# emp3032a.net
KiCad netlist of a schematic drawn in EAGLE
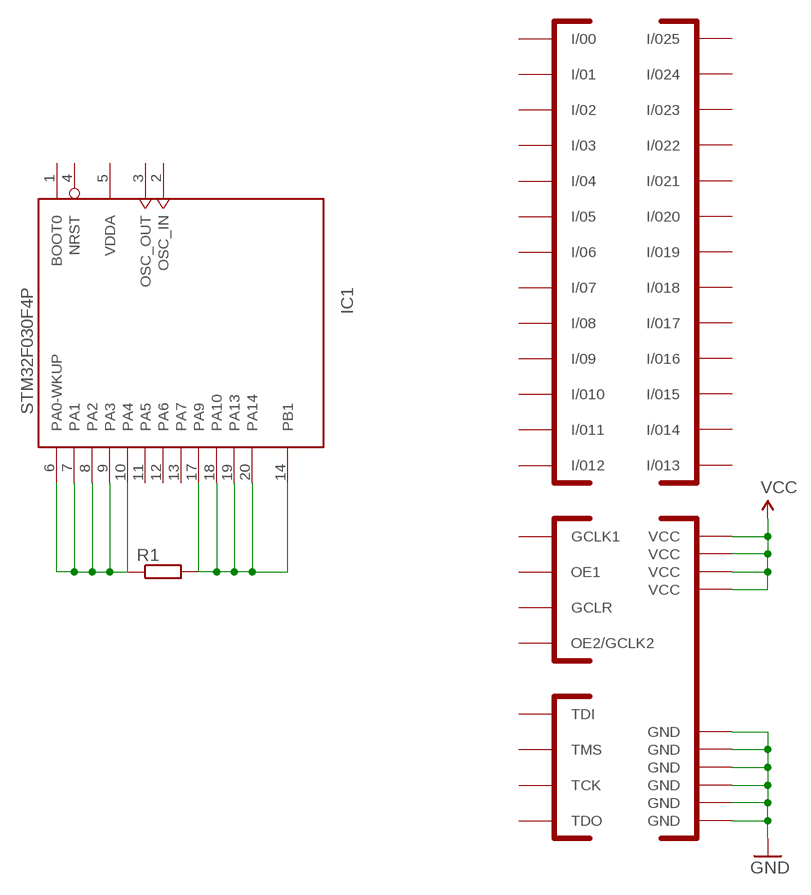
[diagram p0: schematic, sheet 1]
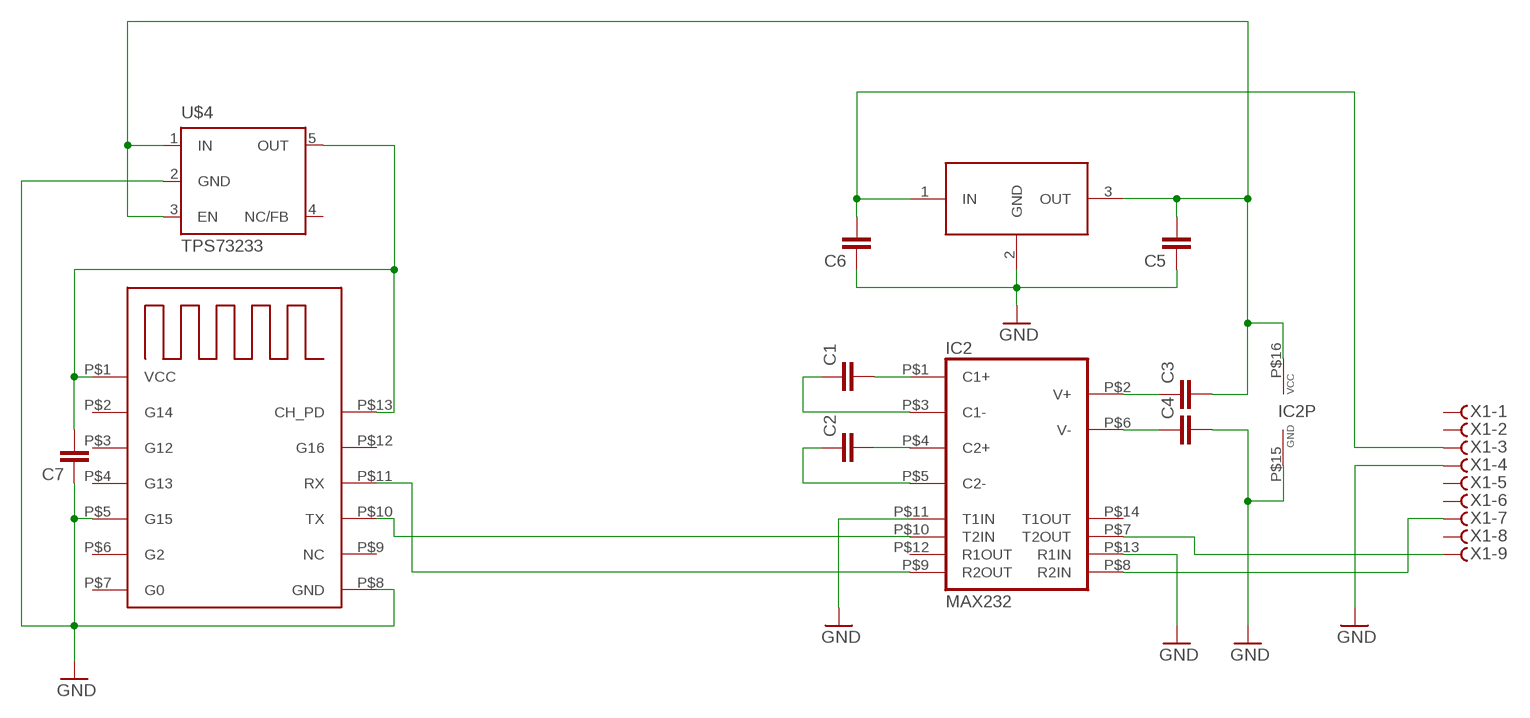
[diagram p1: schematic, sheet 2]

(export (version "E")
  (design (tool "Eeschema 10.0.6"))
  (components
    (comp (ref "IC1")
      (value "STM32F030F4P")
      (footprint "eagle-import:TSSOP20-I")
      (libsource (lib "eagle-import") (part "STM32F030FP4"))
    )
    (comp (ref "R1")
      (value "R1206")
      (footprint "eagle-import:R1206")
      (libsource (lib "eagle-import") (part "R1206"))
    )
    (comp (ref "U$1")
      (value "EPM3032")
      (footprint "eagle-import:TQFP44")
      (libsource (lib "eagle-import") (part "EPM3032"))
    )
    (comp (ref "C1")
      (value "C-EUC1206K")
      (footprint "eagle-import:C1206K")
      (libsource (lib "eagle-import") (part "C-EUC1206K"))
    )
    (comp (ref "C2")
      (value "C-EUC1206K")
      (footprint "eagle-import:C1206K")
      (libsource (lib "eagle-import") (part "C-EUC1206K"))
    )
    (comp (ref "C3")
      (value "C-EUC1206K")
      (footprint "eagle-import:C1206K")
      (libsource (lib "eagle-import") (part "C-EUC1206K"))
    )
    (comp (ref "C4")
      (value "C-EUC1206K")
      (footprint "eagle-import:C1206K")
      (libsource (lib "eagle-import") (part "C-EUC1206K"))
    )
    (comp (ref "C5")
      (value "C-EUC1206K")
      (footprint "eagle-import:C1206K")
      (libsource (lib "eagle-import") (part "C-EUC1206K"))
    )
    (comp (ref "C6")
      (value "C-EUC1206K")
      (footprint "eagle-import:C1206K")
      (libsource (lib "eagle-import") (part "C-EUC1206K"))
    )
    (comp (ref "C7")
      (value "C-EUC1206K")
      (footprint "eagle-import:C1206K")
      (libsource (lib "eagle-import") (part "C-EUC1206K"))
    )
    (comp (ref "IC2")
      (value "MAX232")
      (footprint "eagle-import:DIL16")
      (libsource (lib "eagle-import") (part "MAX232"))
    )
    (comp (ref "U$2")
      (value "ESP03")
      (footprint "eagle-import:ESP03")
      (libsource (lib "eagle-import") (part "ESP03"))
    )
    (comp (ref "U$3")
      (value "LM78M05BG")
      (footprint "eagle-import:DPACK")
      (libsource (lib "eagle-import") (part "LM78M05BG"))
    )
    (comp (ref "U$4")
      (value "TPS73233")
      (footprint "eagle-import:SOT23-DBV")
      (libsource (lib "eagle-import") (part "TPS73233"))
    )
    (comp (ref "X1")
      (value "F09HS")
      (footprint "eagle-import:F09H")
      (libsource (lib "eagle-import") (part "F09?SH"))
    )
  )
  (nets
    (net (code "1") (name "GCLK1") (class "Default")
      (node (ref "U$1") (pin "37") (pinfunction "GCLK1_37") (pintype "power_in"))
    )
    (net (code "2") (name "GCLR") (class "Default")
      (node (ref "U$1") (pin "39") (pinfunction "GCLR_39") (pintype "power_in"))
    )
    (net (code "3") (name "GND") (class "Default")
      (node (ref "C4") (pin "2") (pinfunction "2_2") (pintype "passive"))
      (node (ref "C5") (pin "1") (pinfunction "1_1") (pintype "passive"))
      (node (ref "C6") (pin "1") (pinfunction "1_1") (pintype "passive"))
      (node (ref "C7") (pin "1") (pinfunction "1_1") (pintype "passive"))
      (node (ref "IC2") (pin "P$11") (pinfunction "T1IN_P$11") (pintype "input"))
      (node (ref "IC2") (pin "P$13") (pinfunction "R1IN_P$13") (pintype "input"))
      (node (ref "IC2") (pin "P$15") (pinfunction "GND_P$15") (pintype "power_in"))
      (node (ref "U$1") (pin "11") (pinfunction "GND_11") (pintype "power_in"))
      (node (ref "U$1") (pin "16") (pinfunction "GND_16") (pintype "power_in"))
      (node (ref "U$1") (pin "24") (pinfunction "GND_24") (pintype "power_in"))
      (node (ref "U$1") (pin "30") (pinfunction "GND_30") (pintype "power_in"))
      (node (ref "U$1") (pin "36") (pinfunction "GND_36") (pintype "power_in"))
      (node (ref "U$1") (pin "4") (pinfunction "GND_4") (pintype "power_in"))
      (node (ref "U$2") (pin "P$5") (pinfunction "G15_P$5") (pintype "bidirectional"))
      (node (ref "U$2") (pin "P$8") (pinfunction "GND_P$8") (pintype "bidirectional"))
      (node (ref "U$3") (pin "2") (pinfunction "GND_2") (pintype "bidirectional"))
      (node (ref "U$4") (pin "2") (pinfunction "GND_2") (pintype "power_in"))
      (node (ref "X1") (pin "4") (pinfunction "F_4") (pintype "passive"))
    )
    (net (code "4") (name "I{slash}00") (class "Default")
      (node (ref "U$1") (pin "2") (pinfunction "I/00_2") (pintype "power_in"))
    )
    (net (code "5") (name "I{slash}01") (class "Default")
      (node (ref "U$1") (pin "5") (pinfunction "I/01_5") (pintype "power_in"))
    )
    (net (code "6") (name "I{slash}02") (class "Default")
      (node (ref "U$1") (pin "6") (pinfunction "I/02_6") (pintype "power_in"))
    )
    (net (code "7") (name "I{slash}03") (class "Default")
      (node (ref "U$1") (pin "12") (pinfunction "I/03_12") (pintype "power_in"))
    )
    (net (code "8") (name "I{slash}04") (class "Default")
      (node (ref "U$1") (pin "13") (pinfunction "I/04_13") (pintype "power_in"))
    )
    (net (code "9") (name "I{slash}05") (class "Default")
      (node (ref "U$1") (pin "14") (pinfunction "I/05_14") (pintype "power_in"))
    )
    (net (code "10") (name "I{slash}06") (class "Default")
      (node (ref "U$1") (pin "15") (pinfunction "I/06_15") (pintype "power_in"))
    )
    (net (code "11") (name "I{slash}07") (class "Default")
      (node (ref "U$1") (pin "25") (pinfunction "I/07_25") (pintype "power_in"))
    )
    (net (code "12") (name "I{slash}08") (class "Default")
      (node (ref "U$1") (pin "44") (pinfunction "I/08_44") (pintype "power_in"))
    )
    (net (code "13") (name "I{slash}09") (class "Default")
      (node (ref "U$1") (pin "43") (pinfunction "I/09_43") (pintype "power_in"))
    )
    (net (code "14") (name "I{slash}010") (class "Default")
      (node (ref "U$1") (pin "42") (pinfunction "I/010_42") (pintype "power_in"))
    )
    (net (code "15") (name "I{slash}011") (class "Default")
      (node (ref "U$1") (pin "35") (pinfunction "I/011_35") (pintype "power_in"))
    )
    (net (code "16") (name "I{slash}012") (class "Default")
      (node (ref "U$1") (pin "34") (pinfunction "I/012_34") (pintype "power_in"))
    )
    (net (code "17") (name "I{slash}013") (class "Default")
      (node (ref "U$1") (pin "28") (pinfunction "I/013_28") (pintype "power_in"))
    )
    (net (code "18") (name "I{slash}014") (class "Default")
      (node (ref "U$1") (pin "27") (pinfunction "I/014_27") (pintype "power_in"))
    )
    (net (code "19") (name "I{slash}015") (class "Default")
      (node (ref "U$1") (pin "33") (pinfunction "I/015_33") (pintype "power_in"))
    )
    (net (code "20") (name "I{slash}016") (class "Default")
      (node (ref "U$1") (pin "21") (pinfunction "I/016_21") (pintype "power_in"))
    )
    (net (code "21") (name "I{slash}017") (class "Default")
      (node (ref "U$1") (pin "22") (pinfunction "I/017_22") (pintype "power_in"))
    )
    (net (code "22") (name "I{slash}018") (class "Default")
      (node (ref "U$1") (pin "23") (pinfunction "I/018_23") (pintype "power_in"))
    )
    (net (code "23") (name "I{slash}019") (class "Default")
      (node (ref "U$1") (pin "31") (pinfunction "I/019_31") (pintype "power_in"))
    )
    (net (code "24") (name "I{slash}020") (class "Default")
      (node (ref "U$1") (pin "18") (pinfunction "I/020_18") (pintype "power_in"))
    )
    (net (code "25") (name "I{slash}021") (class "Default")
      (node (ref "U$1") (pin "19") (pinfunction "I/021_19") (pintype "power_in"))
    )
    (net (code "26") (name "I{slash}022") (class "Default")
      (node (ref "U$1") (pin "8") (pinfunction "I/022_8") (pintype "power_in"))
    )
    (net (code "27") (name "I{slash}023") (class "Default")
      (node (ref "U$1") (pin "20") (pinfunction "I/023_20") (pintype "power_in"))
    )
    (net (code "28") (name "I{slash}024") (class "Default")
      (node (ref "U$1") (pin "10") (pinfunction "I/024_10") (pintype "power_in"))
    )
    (net (code "29") (name "I{slash}025") (class "Default")
      (node (ref "U$1") (pin "3") (pinfunction "I/025_3") (pintype "power_in"))
    )
    (net (code "30") (name "Net-(IC1A-PA0-WKUP)") (class "Default")
      (node (ref "IC1") (pin "10") (pinfunction "PA4_10") (pintype "bidirectional"))
      (node (ref "IC1") (pin "6") (pinfunction "PA0-WKUP_6") (pintype "bidirectional"))
      (node (ref "IC1") (pin "7") (pinfunction "PA1_7") (pintype "bidirectional"))
      (node (ref "IC1") (pin "8") (pinfunction "PA2_8") (pintype "bidirectional"))
      (node (ref "IC1") (pin "9") (pinfunction "PA3_9") (pintype "bidirectional"))
      (node (ref "R1") (pin "1") (pinfunction "1_1") (pintype "passive"))
    )
    (net (code "31") (name "Net-(IC1A-PA10)") (class "Default")
      (node (ref "IC1") (pin "14") (pinfunction "PB1_14") (pintype "bidirectional"))
      (node (ref "IC1") (pin "17") (pinfunction "PA9_17") (pintype "bidirectional"))
      (node (ref "IC1") (pin "18") (pinfunction "PA10_18") (pintype "bidirectional"))
      (node (ref "IC1") (pin "19") (pinfunction "PA13_19") (pintype "bidirectional"))
      (node (ref "IC1") (pin "20") (pinfunction "PA14_20") (pintype "bidirectional"))
      (node (ref "R1") (pin "2") (pinfunction "2_2") (pintype "passive"))
    )
    (net (code "32") (name "Net-(IC2A-C1+)") (class "Default")
      (node (ref "C1") (pin "2") (pinfunction "2_2") (pintype "passive"))
      (node (ref "IC2") (pin "P$1") (pinfunction "C1+_P$1") (pintype "bidirectional"))
    )
    (net (code "33") (name "Net-(IC2A-C1-)") (class "Default")
      (node (ref "C1") (pin "1") (pinfunction "1_1") (pintype "passive"))
      (node (ref "IC2") (pin "P$3") (pinfunction "C1-_P$3") (pintype "bidirectional"))
    )
    (net (code "34") (name "Net-(IC2A-C2+)") (class "Default")
      (node (ref "C2") (pin "2") (pinfunction "2_2") (pintype "passive"))
      (node (ref "IC2") (pin "P$4") (pinfunction "C2+_P$4") (pintype "bidirectional"))
    )
    (net (code "35") (name "Net-(IC2A-C2-)") (class "Default")
      (node (ref "C2") (pin "1") (pinfunction "1_1") (pintype "passive"))
      (node (ref "IC2") (pin "P$5") (pinfunction "C2-_P$5") (pintype "bidirectional"))
    )
    (net (code "36") (name "Net-(IC2A-R2IN)") (class "Default")
      (node (ref "IC2") (pin "P$8") (pinfunction "R2IN_P$8") (pintype "input"))
      (node (ref "X1") (pin "7") (pinfunction "F_7") (pintype "passive"))
    )
    (net (code "37") (name "Net-(IC2A-R2OUT)") (class "Default")
      (node (ref "IC2") (pin "P$9") (pinfunction "R2OUT_P$9") (pintype "output"))
      (node (ref "U$2") (pin "P$11") (pinfunction "RX_P$11") (pintype "bidirectional"))
    )
    (net (code "38") (name "Net-(IC2A-T2IN)") (class "Default")
      (node (ref "IC2") (pin "P$10") (pinfunction "T2IN_P$10") (pintype "input"))
      (node (ref "U$2") (pin "P$10") (pinfunction "TX_P$10") (pintype "bidirectional"))
    )
    (net (code "39") (name "Net-(IC2A-T2OUT)") (class "Default")
      (node (ref "IC2") (pin "P$7") (pinfunction "T2OUT_P$7") (pintype "output"))
      (node (ref "X1") (pin "9") (pinfunction "F_9") (pintype "passive"))
    )
    (net (code "40") (name "Net-(IC2A-V+)") (class "Default")
      (node (ref "C3") (pin "1") (pinfunction "1_1") (pintype "passive"))
      (node (ref "IC2") (pin "P$2") (pinfunction "V+_P$2") (pintype "bidirectional"))
    )
    (net (code "41") (name "Net-(IC2A-V-)") (class "Default")
      (node (ref "C4") (pin "1") (pinfunction "1_1") (pintype "passive"))
      (node (ref "IC2") (pin "P$6") (pinfunction "V-_P$6") (pintype "bidirectional"))
    )
    (net (code "42") (name "Net-(IC2B-VCC)") (class "Default")
      (node (ref "C3") (pin "2") (pinfunction "2_2") (pintype "passive"))
      (node (ref "C5") (pin "2") (pinfunction "2_2") (pintype "passive"))
      (node (ref "IC2") (pin "P$16") (pinfunction "VCC_P$16") (pintype "power_in"))
      (node (ref "U$3") (pin "3") (pinfunction "OUT_3") (pintype "bidirectional"))
      (node (ref "U$4") (pin "1") (pinfunction "IN_1") (pintype "input"))
      (node (ref "U$4") (pin "3") (pinfunction "EN_3") (pintype "input"))
    )
    (net (code "43") (name "Net-(U$2-CH_PD)") (class "Default")
      (node (ref "C7") (pin "2") (pinfunction "2_2") (pintype "passive"))
      (node (ref "U$2") (pin "P$1") (pinfunction "VCC_P$1") (pintype "bidirectional"))
      (node (ref "U$2") (pin "P$13") (pinfunction "CH_PD_P$13") (pintype "bidirectional"))
      (node (ref "U$4") (pin "5") (pinfunction "OUT_5") (pintype "passive"))
    )
    (net (code "44") (name "Net-(U$3-IN)") (class "Default")
      (node (ref "C6") (pin "2") (pinfunction "2_2") (pintype "passive"))
      (node (ref "U$3") (pin "1") (pinfunction "IN_1") (pintype "bidirectional"))
      (node (ref "X1") (pin "3") (pinfunction "F_3") (pintype "passive"))
    )
    (net (code "45") (name "OE1") (class "Default")
      (node (ref "U$1") (pin "38") (pinfunction "OE1_38") (pintype "power_in"))
    )
    (net (code "46") (name "OE2{slash}GCLK2") (class "Default")
      (node (ref "U$1") (pin "40") (pinfunction "OE2/GCLK2_40") (pintype "power_in"))
    )
    (net (code "47") (name "TCK") (class "Default")
      (node (ref "U$1") (pin "26") (pinfunction "TCK_26") (pintype "power_in"))
    )
    (net (code "48") (name "TDI") (class "Default")
      (node (ref "U$1") (pin "1") (pinfunction "TDI_1") (pintype "power_in"))
    )
    (net (code "49") (name "TDO") (class "Default")
      (node (ref "U$1") (pin "32") (pinfunction "TDO_32") (pintype "power_in"))
    )
    (net (code "50") (name "TMS") (class "Default")
      (node (ref "U$1") (pin "7") (pinfunction "TMS_7") (pintype "power_in"))
    )
    (net (code "51") (name "VCC") (class "Default")
      (node (ref "U$1") (pin "17") (pinfunction "VCC_17") (pintype "power_in"))
      (node (ref "U$1") (pin "29") (pinfunction "VCC_29") (pintype "power_in"))
      (node (ref "U$1") (pin "41") (pinfunction "VCC_41") (pintype "power_in"))
      (node (ref "U$1") (pin "9") (pinfunction "VCC_9") (pintype "power_in"))
    )
    (net (code "52") (name "VDDA") (class "Default")
      (node (ref "IC1") (pin "5") (pinfunction "VDDA_5") (pintype "power_in"))
    )
    (net (code "53") (name "unconnected-(IC1A-BOOT0-Pad1)") (class "Default")
      (node (ref "IC1") (pin "1") (pinfunction "BOOT0_1") (pintype "input"))
    )
    (net (code "54") (name "unconnected-(IC1A-NRST-Pad4)") (class "Default")
      (node (ref "IC1") (pin "4") (pinfunction "NRST_4") (pintype "bidirectional"))
    )
    (net (code "55") (name "unconnected-(IC1A-OSC_IN-Pad2)") (class "Default")
      (node (ref "IC1") (pin "2") (pinfunction "OSC_IN_2") (pintype "bidirectional"))
    )
    (net (code "56") (name "unconnected-(IC1A-OSC_OUT-Pad3)") (class "Default")
      (node (ref "IC1") (pin "3") (pinfunction "OSC_OUT_3") (pintype "bidirectional"))
    )
    (net (code "57") (name "unconnected-(IC1A-PA5-Pad11)") (class "Default")
      (node (ref "IC1") (pin "11") (pinfunction "PA5_11") (pintype "bidirectional"))
    )
    (net (code "58") (name "unconnected-(IC1A-PA6-Pad12)") (class "Default")
      (node (ref "IC1") (pin "12") (pinfunction "PA6_12") (pintype "bidirectional"))
    )
    (net (code "59") (name "unconnected-(IC1A-PA7-Pad13)") (class "Default")
      (node (ref "IC1") (pin "13") (pinfunction "PA7_13") (pintype "bidirectional"))
    )
    (net (code "60") (name "unconnected-(IC2A-R1OUT-PadP$12)") (class "Default")
      (node (ref "IC2") (pin "P$12") (pinfunction "R1OUT_P$12") (pintype "output"))
    )
    (net (code "61") (name "unconnected-(IC2A-T1OUT-PadP$14)") (class "Default")
      (node (ref "IC2") (pin "P$14") (pinfunction "T1OUT_P$14") (pintype "output"))
    )
    (net (code "62") (name "unconnected-(U$2-G0-PadP$7)") (class "Default")
      (node (ref "U$2") (pin "P$7") (pinfunction "G0_P$7") (pintype "bidirectional"))
    )
    (net (code "63") (name "unconnected-(U$2-G2-PadP$6)") (class "Default")
      (node (ref "U$2") (pin "P$6") (pinfunction "G2_P$6") (pintype "bidirectional"))
    )
    (net (code "64") (name "unconnected-(U$2-G12-PadP$3)") (class "Default")
      (node (ref "U$2") (pin "P$3") (pinfunction "G12_P$3") (pintype "bidirectional"))
    )
    (net (code "65") (name "unconnected-(U$2-G13-PadP$4)") (class "Default")
      (node (ref "U$2") (pin "P$4") (pinfunction "G13_P$4") (pintype "bidirectional"))
    )
    (net (code "66") (name "unconnected-(U$2-G14-PadP$2)") (class "Default")
      (node (ref "U$2") (pin "P$2") (pinfunction "G14_P$2") (pintype "bidirectional"))
    )
    (net (code "67") (name "unconnected-(U$2-G16-PadP$12)") (class "Default")
      (node (ref "U$2") (pin "P$12") (pinfunction "G16_P$12") (pintype "bidirectional"))
    )
    (net (code "68") (name "unconnected-(U$2-NC-PadP$9)") (class "Default")
      (node (ref "U$2") (pin "P$9") (pinfunction "NC_P$9") (pintype "bidirectional"))
    )
    (net (code "69") (name "unconnected-(U$4-NC{slash}FB-Pad4)") (class "Default")
      (node (ref "U$4") (pin "4") (pinfunction "NC/FB_4") (pintype "passive"))
    )
    (net (code "70") (name "unconnected-(X1A-F-Pad1)") (class "Default")
      (node (ref "X1") (pin "1") (pinfunction "F_1") (pintype "passive"))
    )
    (net (code "71") (name "unconnected-(X1B-F-Pad2)") (class "Default")
      (node (ref "X1") (pin "2") (pinfunction "F_2") (pintype "passive"))
    )
    (net (code "72") (name "unconnected-(X1E-F-Pad5)") (class "Default")
      (node (ref "X1") (pin "5") (pinfunction "F_5") (pintype "passive"))
    )
    (net (code "73") (name "unconnected-(X1F-F-Pad6)") (class "Default")
      (node (ref "X1") (pin "6") (pinfunction "F_6") (pintype "passive"))
    )
    (net (code "74") (name "unconnected-(X1H-F-Pad8)") (class "Default")
      (node (ref "X1") (pin "8") (pinfunction "F_8") (pintype "passive"))
    )
  )
)
